# front_light.net
KiCad netlist of a schematic drawn in EAGLE
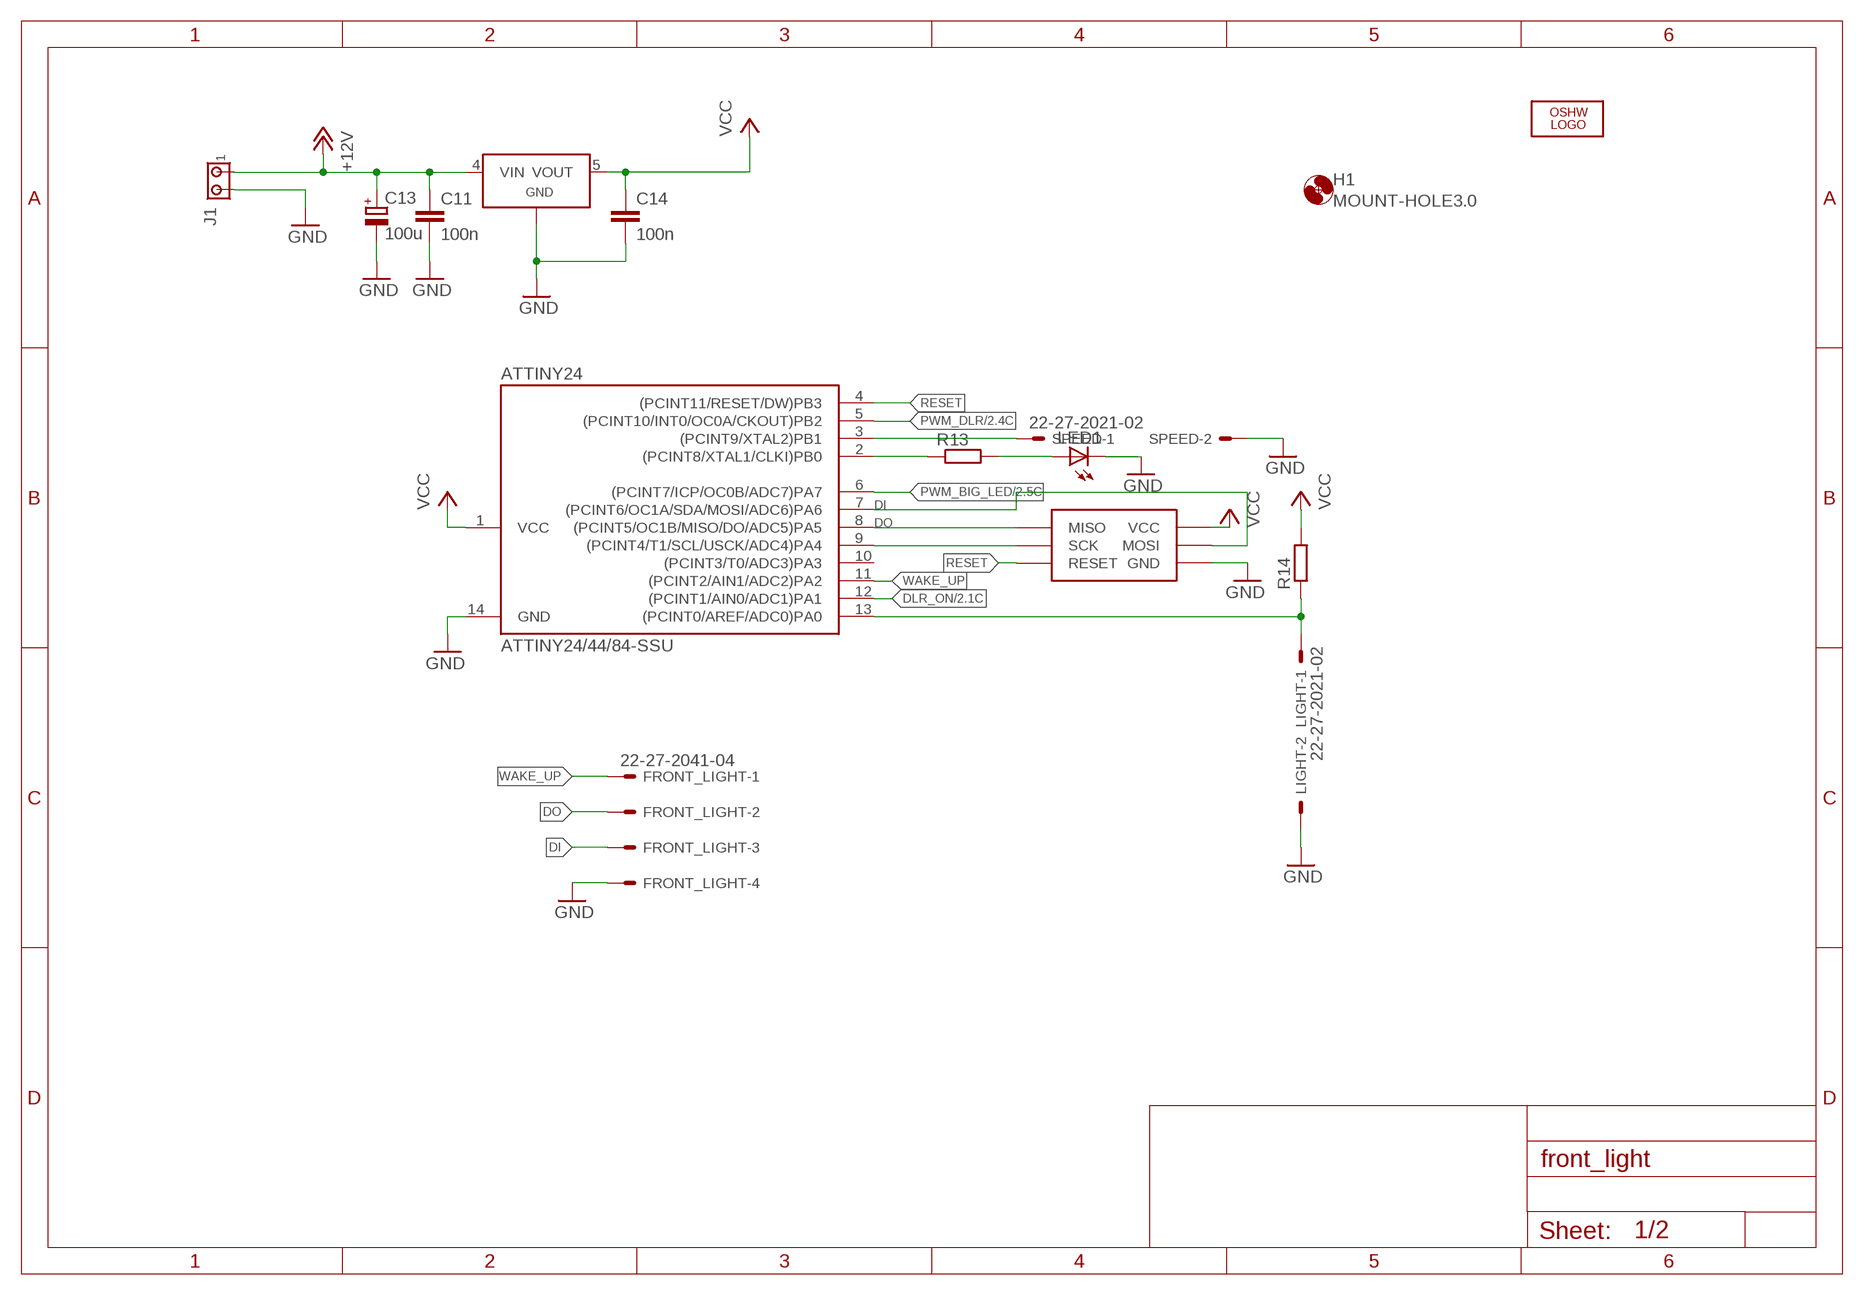
[diagram p0: schematic, sheet 1]
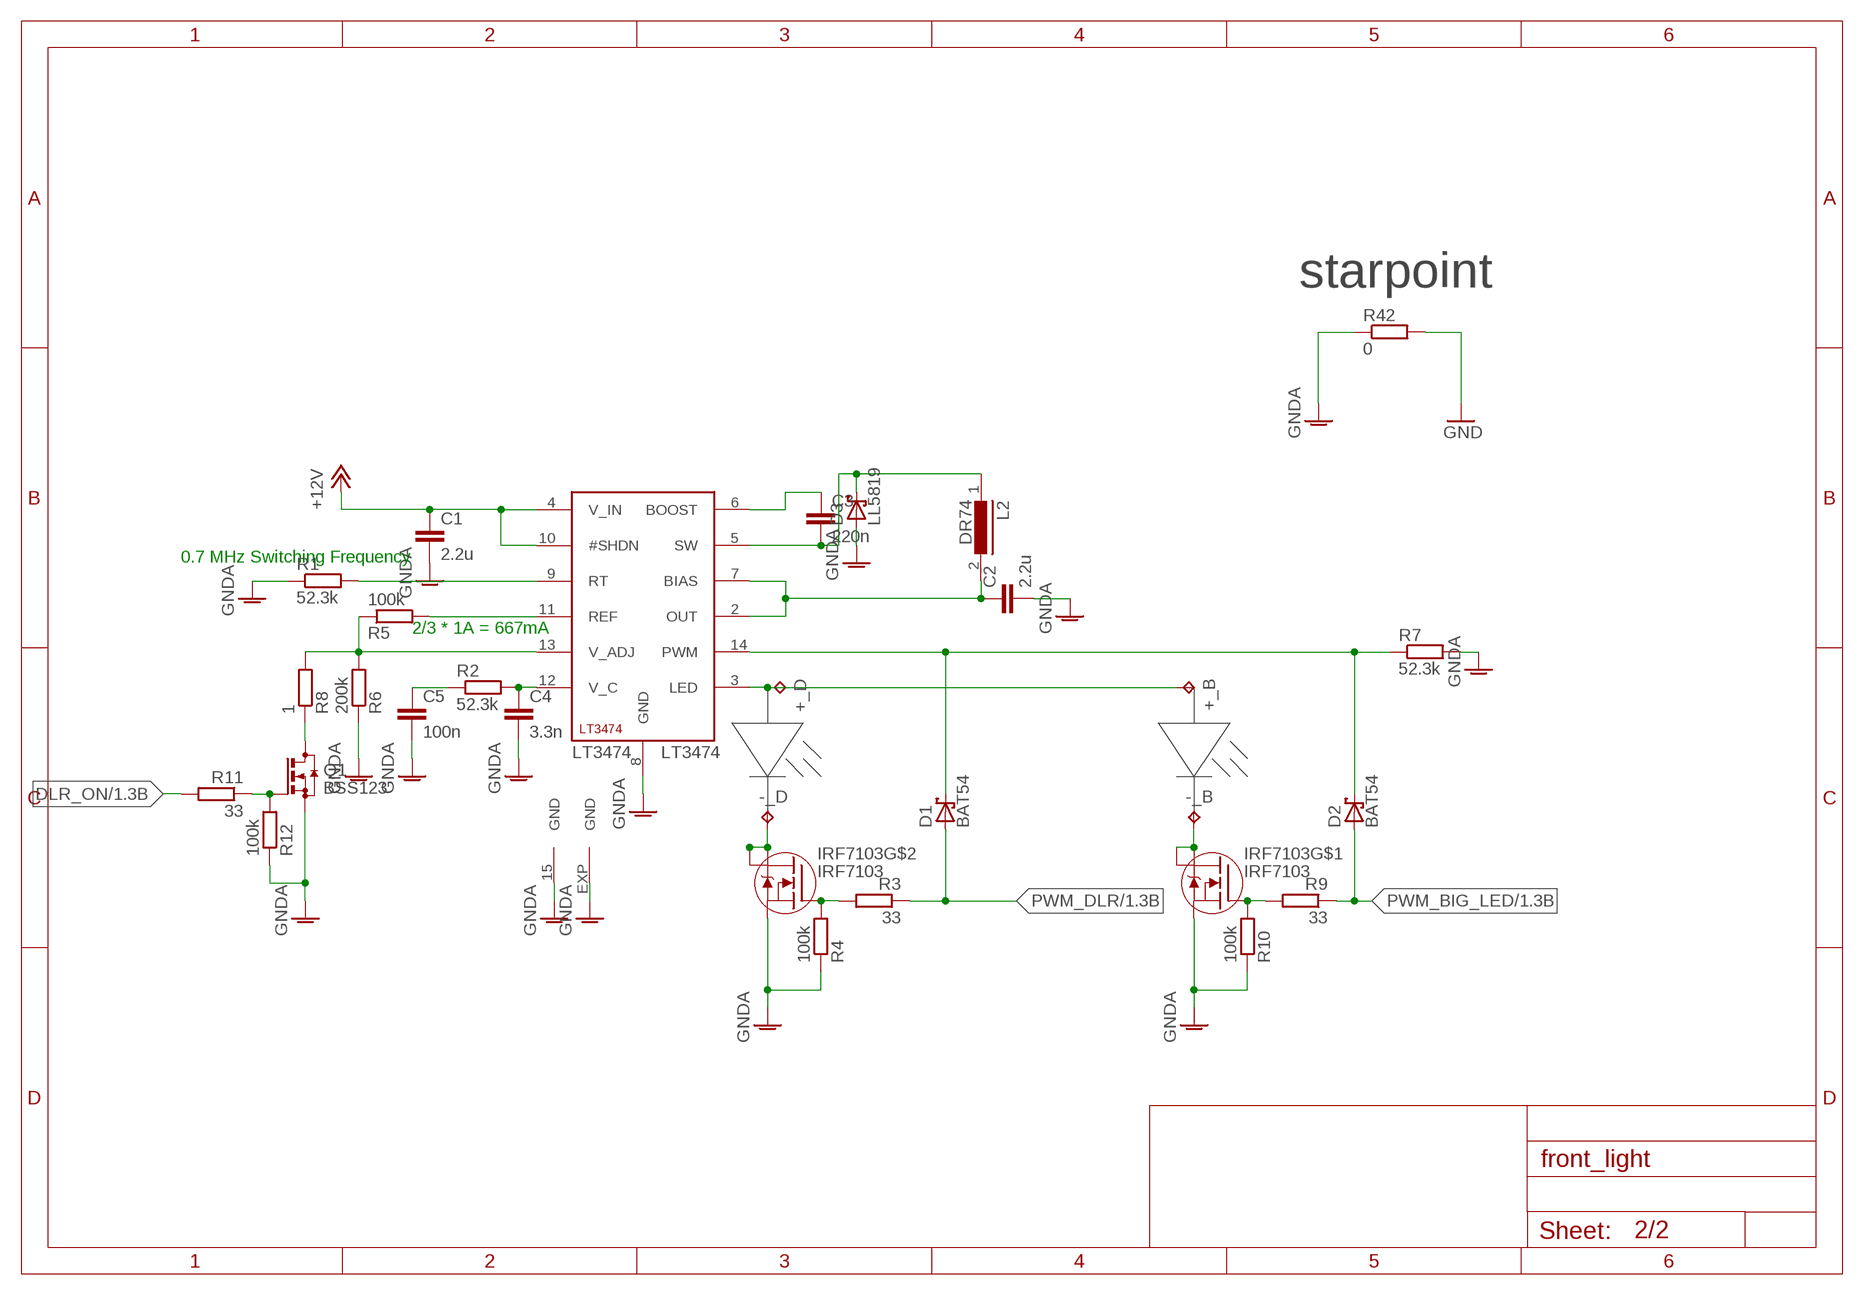
[diagram p1: schematic, sheet 2]

(export (version "E")
  (design (tool "Eeschema 10.0.6"))
  (components
    (comp (ref "+_B")
      (value "TPTP20SQ")
      (footprint "eagle-import:TP20SQ")
      (libsource (lib "eagle-import") (part "TPTP20SQ"))
    )
    (comp (ref "+_D")
      (value "TPTP20SQ")
      (footprint "eagle-import:TP20SQ")
      (libsource (lib "eagle-import") (part "TPTP20SQ"))
    )
    (comp (ref "-_B")
      (value "TPTP20SQ")
      (footprint "eagle-import:TP20SQ")
      (libsource (lib "eagle-import") (part "TPTP20SQ"))
    )
    (comp (ref "-_D")
      (value "TPTP20SQ")
      (footprint "eagle-import:TP20SQ")
      (libsource (lib "eagle-import") (part "TPTP20SQ"))
    )
    (comp (ref "C1")
      (value "2.2u")
      (footprint "eagle-import:C0805")
      (libsource (lib "eagle-import") (part "C-EUC0805"))
    )
    (comp (ref "C2")
      (value "2.2u")
      (footprint "eagle-import:C0805")
      (libsource (lib "eagle-import") (part "C-EUC0805"))
    )
    (comp (ref "C3")
      (value "220n")
      (footprint "eagle-import:C0603")
      (libsource (lib "eagle-import") (part "C-EUC0603"))
    )
    (comp (ref "C4")
      (value "3.3n")
      (footprint "eagle-import:C0603")
      (libsource (lib "eagle-import") (part "C-EUC0603"))
    )
    (comp (ref "C5")
      (value "100n")
      (footprint "eagle-import:C0603")
      (libsource (lib "eagle-import") (part "C-EUC0603"))
    )
    (comp (ref "D1")
      (value "BAT54")
      (footprint "eagle-import:SOT23")
      (libsource (lib "eagle-import") (part "BAT54"))
    )
    (comp (ref "D2")
      (value "BAT54")
      (footprint "eagle-import:SOT23")
      (libsource (lib "eagle-import") (part "BAT54"))
    )
    (comp (ref "D3")
      (value "LL5819")
      (footprint "eagle-import:MELF-MLL41")
      (libsource (lib "eagle-import") (part "DIODESCHOTTKY"))
    )
    (comp (ref "IRF7103")
      (value "IRF7103")
      (footprint "eagle-import:SO8-2")
      (libsource (lib "eagle-import") (part "IRF7103"))
    )
    (comp (ref "L2")
      (value "DR74")
      (footprint "eagle-import:DR74")
      (libsource (lib "eagle-import") (part "DR74"))
    )
    (comp (ref "LT3474")
      (value "LT3474")
      (footprint "eagle-import:TSSOP16_BA")
      (libsource (lib "eagle-import") (part "LT3474"))
    )
    (comp (ref "Q1")
      (value "BSS123")
      (footprint "eagle-import:SOT23")
      (libsource (lib "eagle-import") (part "BSS123"))
    )
    (comp (ref "R1")
      (value "52.3k")
      (footprint "eagle-import:R0603")
      (libsource (lib "eagle-import") (part "resistor_R-EU_R0603"))
    )
    (comp (ref "R2")
      (value "52.3k")
      (footprint "eagle-import:R0603")
      (libsource (lib "eagle-import") (part "resistor_R-EU_R0603"))
    )
    (comp (ref "R3")
      (value "33")
      (footprint "eagle-import:R0603")
      (libsource (lib "eagle-import") (part "resistor_R-EU_R0603"))
    )
    (comp (ref "R4")
      (value "100k")
      (footprint "eagle-import:R0603")
      (libsource (lib "eagle-import") (part "resistor_R-EU_R0603"))
    )
    (comp (ref "R5")
      (value "100k")
      (footprint "eagle-import:R0603")
      (libsource (lib "eagle-import") (part "resistor_R-EU_R0603"))
    )
    (comp (ref "R6")
      (value "200k")
      (footprint "eagle-import:R0603")
      (libsource (lib "eagle-import") (part "resistor_R-EU_R0603"))
    )
    (comp (ref "R7")
      (value "52.3k")
      (footprint "eagle-import:R0603")
      (libsource (lib "eagle-import") (part "resistor_R-EU_R0603"))
    )
    (comp (ref "R8")
      (value "1")
      (footprint "eagle-import:R0603")
      (libsource (lib "eagle-import") (part "resistor_R-EU_R0603"))
    )
    (comp (ref "R9")
      (value "33")
      (footprint "eagle-import:R0603")
      (libsource (lib "eagle-import") (part "resistor_R-EU_R0603"))
    )
    (comp (ref "R10")
      (value "100k")
      (footprint "eagle-import:R0603")
      (libsource (lib "eagle-import") (part "resistor_R-EU_R0603"))
    )
    (comp (ref "R11")
      (value "33")
      (footprint "eagle-import:R0603")
      (libsource (lib "eagle-import") (part "resistor_R-EU_R0603"))
    )
    (comp (ref "R12")
      (value "100k")
      (footprint "eagle-import:R0603")
      (libsource (lib "eagle-import") (part "resistor_R-EU_R0603"))
    )
    (comp (ref "R42")
      (value "0")
      (footprint "eagle-import:R0603")
      (libsource (lib "eagle-import") (part "R-EU_R0603"))
    )
    (comp (ref "ATTINY24")
      (value "ATTINY24/44/84-SSU")
      (footprint "eagle-import:SOIC14")
      (libsource (lib "eagle-import") (part "ATTINY24/44/84-SSU"))
    )
    (comp (ref "C11")
      (value "100n")
      (footprint "eagle-import:C0603")
      (libsource (lib "eagle-import") (part "C-EUC0603"))
    )
    (comp (ref "C13")
      (value "100u")
      (footprint "eagle-import:PANASONIC_E")
      (libsource (lib "eagle-import") (part "CPOL-EUE"))
    )
    (comp (ref "C14")
      (value "100n")
      (footprint "eagle-import:C0603")
      (libsource (lib "eagle-import") (part "C-EUC0603"))
    )
    (comp (ref "FRONT_LIGHT")
      (value "22-27-2041-04")
      (footprint "eagle-import:6410-04")
      (libsource (lib "eagle-import") (part "22-?-0427-2041"))
    )
    (comp (ref "H1")
      (value "MOUNT-HOLE3.0")
      (footprint "eagle-import:3,0")
      (libsource (lib "eagle-import") (part "MOUNT-HOLE3.0"))
    )
    (comp (ref "J1")
      (value "MTA02-156")
      (footprint "eagle-import:1X2MTA")
      (libsource (lib "eagle-import") (part "MTA02-156"))
    )
    (comp (ref "LED1")
      (value "LEDCHIPLED_0603")
      (footprint "eagle-import:CHIPLED_0603")
      (libsource (lib "eagle-import") (part "LEDCHIPLED_0603"))
    )
    (comp (ref "LIGHT")
      (value "22-27-2021-02")
      (footprint "eagle-import:6410-02")
      (libsource (lib "eagle-import") (part "22-?-0227-2021"))
    )
    (comp (ref "LOGO2")
      (value "OSHW_LOGO_6MILX0150-NT")
      (footprint "eagle-import:OSHW_6X150_NOTEXT")
      (libsource (lib "eagle-import") (part "OSHW_LOGO_6MILX0150-NT"))
    )
    (comp (ref "R13")
      (value "R-EU_R0603")
      (footprint "eagle-import:R0603")
      (libsource (lib "eagle-import") (part "resistor_R-EU_R0603"))
    )
    (comp (ref "R14")
      (value "R-EU_R0603")
      (footprint "eagle-import:R0603")
      (libsource (lib "eagle-import") (part "resistor_R-EU_R0603"))
    )
    (comp (ref "SPEED")
      (value "22-27-2021-02")
      (footprint "eagle-import:6410-02")
      (libsource (lib "eagle-import") (part "22-?-0227-2021"))
    )
    (comp (ref "U$1")
      (value "TPS71530")
      (footprint "eagle-import:SOT23-DBV")
      (libsource (lib "eagle-import") (part "TPS71530"))
    )
    (comp (ref "U$2")
      (value "ISP_SPECIALS")
      (footprint "eagle-import:ISP_RM2_00_STRAIGHT")
      (libsource (lib "eagle-import") (part "ISP_SPECIALS"))
    )
  )
  (nets
    (net (code "1") (name "+12V") (class "Default")
      (node (ref "C1") (pin "1") (pinfunction "1_1") (pintype "passive"))
      (node (ref "C11") (pin "1") (pinfunction "1_1") (pintype "passive"))
      (node (ref "C13") (pin "+") (pinfunction "+_+") (pintype "passive"))
      (node (ref "J1") (pin "1") (pinfunction "1_1") (pintype "passive"))
      (node (ref "LT3474") (pin "10") (pinfunction "#SHDN_10") (pintype "passive"))
      (node (ref "LT3474") (pin "4") (pinfunction "V_IN_4") (pintype "passive"))
      (node (ref "U$1") (pin "4") (pinfunction "VIN_4") (pintype "power_in"))
    )
    (net (code "2") (name "DI") (class "Default")
      (node (ref "ATTINY24") (pin "7") (pinfunction "(PCINT6/OC1A/SDA/MOSI/ADC6)PA6_7") (pintype "bidirectional"))
      (node (ref "FRONT_LIGHT") (pin "3") (pinfunction "S_3") (pintype "passive"))
      (node (ref "U$2") (pin "MOSI") (pinfunction "MOSI_MOSI") (pintype "bidirectional"))
    )
    (net (code "3") (name "DLR_ON") (class "Default")
      (node (ref "ATTINY24") (pin "12") (pinfunction "(PCINT1/AIN0/ADC1)PA1_12") (pintype "bidirectional"))
      (node (ref "R11") (pin "2") (pinfunction "2_2") (pintype "passive"))
    )
    (net (code "4") (name "DO") (class "Default")
      (node (ref "ATTINY24") (pin "8") (pinfunction "(PCINT5/OC1B/MISO/DO/ADC5)PA5_8") (pintype "bidirectional"))
      (node (ref "FRONT_LIGHT") (pin "2") (pinfunction "S_2") (pintype "passive"))
      (node (ref "U$2") (pin "RESET") (pinfunction "MISO_RESET") (pintype "bidirectional"))
    )
    (net (code "5") (name "GND") (class "Default")
      (node (ref "ATTINY24") (pin "14") (pinfunction "GND_14") (pintype "power_in"))
      (node (ref "C11") (pin "2") (pinfunction "2_2") (pintype "passive"))
      (node (ref "C13") (pin "-") (pinfunction "-_-") (pintype "passive"))
      (node (ref "C14") (pin "2") (pinfunction "2_2") (pintype "passive"))
      (node (ref "FRONT_LIGHT") (pin "4") (pinfunction "S_4") (pintype "passive"))
      (node (ref "J1") (pin "2") (pinfunction "2_2") (pintype "passive"))
      (node (ref "LED1") (pin "C") (pinfunction "C_C") (pintype "passive"))
      (node (ref "LIGHT") (pin "2") (pinfunction "S_2") (pintype "passive"))
      (node (ref "R42") (pin "2") (pinfunction "2_2") (pintype "passive"))
      (node (ref "SPEED") (pin "2") (pinfunction "S_2") (pintype "passive"))
      (node (ref "U$1") (pin "2") (pinfunction "GND_2") (pintype "power_in"))
      (node (ref "U$2") (pin "VCC") (pinfunction "GND_VCC") (pintype "bidirectional"))
    )
    (net (code "6") (name "GNDA") (class "Default")
      (node (ref "C1") (pin "2") (pinfunction "2_2") (pintype "passive"))
      (node (ref "C2") (pin "2") (pinfunction "2_2") (pintype "passive"))
      (node (ref "C4") (pin "2") (pinfunction "2_2") (pintype "passive"))
      (node (ref "C5") (pin "2") (pinfunction "2_2") (pintype "passive"))
      (node (ref "D3") (pin "A") (pinfunction "A_A") (pintype "passive"))
      (node (ref "IRF7103") (pin "1") (pinfunction "S_1") (pintype "bidirectional"))
      (node (ref "IRF7103") (pin "3") (pinfunction "S_3") (pintype "bidirectional"))
      (node (ref "LT3474") (pin "15") (pinfunction "GND_15") (pintype "power_in"))
      (node (ref "LT3474") (pin "8") (pinfunction "GND_8") (pintype "power_in"))
      (node (ref "LT3474") (pin "EXP") (pinfunction "GND_EXP") (pintype "power_in"))
      (node (ref "Q1") (pin "2") (pinfunction "S_2") (pintype "passive"))
      (node (ref "R1") (pin "1") (pinfunction "1_1") (pintype "passive"))
      (node (ref "R10") (pin "1") (pinfunction "1_1") (pintype "passive"))
      (node (ref "R12") (pin "1") (pinfunction "1_1") (pintype "passive"))
      (node (ref "R4") (pin "1") (pinfunction "1_1") (pintype "passive"))
      (node (ref "R42") (pin "1") (pinfunction "1_1") (pintype "passive"))
      (node (ref "R6") (pin "1") (pinfunction "1_1") (pintype "passive"))
      (node (ref "R7") (pin "2") (pinfunction "2_2") (pintype "passive"))
    )
    (net (code "7") (name "Net-(-_B-PadTP)") (class "Default")
      (node (ref "-_B") (pin "TP") (pinfunction "TP_TP") (pintype "input"))
      (node (ref "IRF7103") (pin "7") (pinfunction "D_7") (pintype "bidirectional"))
      (node (ref "IRF7103") (pin "8") (pinfunction "D_8") (pintype "bidirectional"))
    )
    (net (code "8") (name "Net-(-_D-PadTP)") (class "Default")
      (node (ref "-_D") (pin "TP") (pinfunction "TP_TP") (pintype "input"))
      (node (ref "IRF7103") (pin "5") (pinfunction "D_5") (pintype "bidirectional"))
      (node (ref "IRF7103") (pin "6") (pinfunction "D_6") (pintype "bidirectional"))
    )
    (net (code "9") (name "Net-(ATTINY24-(PCINT0{slash}AREF{slash}ADC0)PA0)") (class "Default")
      (node (ref "ATTINY24") (pin "13") (pinfunction "(PCINT0/AREF/ADC0)PA0_13") (pintype "bidirectional"))
      (node (ref "LIGHT") (pin "1") (pinfunction "S_1") (pintype "passive"))
      (node (ref "R14") (pin "1") (pinfunction "1_1") (pintype "passive"))
    )
    (net (code "10") (name "Net-(ATTINY24-(PCINT4{slash}T1{slash}SCL{slash}USCK{slash}ADC4)PA4)") (class "Default")
      (node (ref "ATTINY24") (pin "9") (pinfunction "(PCINT4/T1/SCL/USCK/ADC4)PA4_9") (pintype "bidirectional"))
      (node (ref "U$2") (pin "SCK") (pinfunction "SCK_SCK") (pintype "bidirectional"))
    )
    (net (code "11") (name "Net-(ATTINY24-(PCINT8{slash}XTAL1{slash}CLKI)PB0)") (class "Default")
      (node (ref "ATTINY24") (pin "2") (pinfunction "(PCINT8/XTAL1/CLKI)PB0_2") (pintype "bidirectional"))
      (node (ref "R13") (pin "1") (pinfunction "1_1") (pintype "passive"))
    )
    (net (code "12") (name "Net-(ATTINY24-(PCINT9{slash}XTAL2)PB1)") (class "Default")
      (node (ref "ATTINY24") (pin "3") (pinfunction "(PCINT9/XTAL2)PB1_3") (pintype "bidirectional"))
      (node (ref "SPEED") (pin "1") (pinfunction "S_1") (pintype "passive"))
    )
    (net (code "13") (name "Net-(C5-Pad1)") (class "Default")
      (node (ref "C5") (pin "1") (pinfunction "1_1") (pintype "passive"))
      (node (ref "R2") (pin "1") (pinfunction "1_1") (pintype "passive"))
    )
    (net (code "14") (name "Net-(D1-C)") (class "Default")
      (node (ref "D1") (pin "3") (pinfunction "C_3") (pintype "passive"))
      (node (ref "D2") (pin "3") (pinfunction "C_3") (pintype "passive"))
      (node (ref "LT3474") (pin "14") (pinfunction "PWM_14") (pintype "passive"))
      (node (ref "R7") (pin "1") (pinfunction "1_1") (pintype "passive"))
    )
    (net (code "15") (name "Net-(IRF7103A-G)") (class "Default")
      (node (ref "IRF7103") (pin "2") (pinfunction "G_2") (pintype "bidirectional"))
      (node (ref "R10") (pin "2") (pinfunction "2_2") (pintype "passive"))
      (node (ref "R9") (pin "2") (pinfunction "2_2") (pintype "passive"))
    )
    (net (code "16") (name "Net-(IRF7103B-G)") (class "Default")
      (node (ref "IRF7103") (pin "4") (pinfunction "G_4") (pintype "bidirectional"))
      (node (ref "R3") (pin "2") (pinfunction "2_2") (pintype "passive"))
      (node (ref "R4") (pin "2") (pinfunction "2_2") (pintype "passive"))
    )
    (net (code "17") (name "Net-(LED1-PadA)") (class "Default")
      (node (ref "LED1") (pin "A") (pinfunction "A_A") (pintype "passive"))
      (node (ref "R13") (pin "2") (pinfunction "2_2") (pintype "passive"))
    )
    (net (code "18") (name "Net-(LT3474A-BIAS)") (class "Default")
      (node (ref "C2") (pin "1") (pinfunction "1_1") (pintype "passive"))
      (node (ref "L2") (pin "2") (pinfunction "2_2") (pintype "passive"))
      (node (ref "LT3474") (pin "2") (pinfunction "OUT_2") (pintype "passive"))
      (node (ref "LT3474") (pin "7") (pinfunction "BIAS_7") (pintype "passive"))
    )
    (net (code "19") (name "Net-(LT3474A-BOOST)") (class "Default")
      (node (ref "C3") (pin "1") (pinfunction "1_1") (pintype "passive"))
      (node (ref "LT3474") (pin "6") (pinfunction "BOOST_6") (pintype "passive"))
    )
    (net (code "20") (name "Net-(LT3474A-LED)") (class "Default")
      (node (ref "+_B") (pin "TP") (pinfunction "TP_TP") (pintype "input"))
      (node (ref "+_D") (pin "TP") (pinfunction "TP_TP") (pintype "input"))
      (node (ref "LT3474") (pin "3") (pinfunction "LED_3") (pintype "passive"))
    )
    (net (code "21") (name "Net-(LT3474A-REF)") (class "Default")
      (node (ref "LT3474") (pin "11") (pinfunction "REF_11") (pintype "passive"))
      (node (ref "R5") (pin "2") (pinfunction "2_2") (pintype "passive"))
    )
    (net (code "22") (name "Net-(LT3474A-RT)") (class "Default")
      (node (ref "LT3474") (pin "9") (pinfunction "RT_9") (pintype "passive"))
      (node (ref "R1") (pin "2") (pinfunction "2_2") (pintype "passive"))
    )
    (net (code "23") (name "Net-(LT3474A-SW)") (class "Default")
      (node (ref "C3") (pin "2") (pinfunction "2_2") (pintype "passive"))
      (node (ref "D3") (pin "C") (pinfunction "C_C") (pintype "passive"))
      (node (ref "L2") (pin "1") (pinfunction "1_1") (pintype "passive"))
      (node (ref "LT3474") (pin "5") (pinfunction "SW_5") (pintype "passive"))
    )
    (net (code "24") (name "Net-(LT3474A-V_ADJ)") (class "Default")
      (node (ref "LT3474") (pin "13") (pinfunction "V_ADJ_13") (pintype "passive"))
      (node (ref "R5") (pin "1") (pinfunction "1_1") (pintype "passive"))
      (node (ref "R6") (pin "2") (pinfunction "2_2") (pintype "passive"))
      (node (ref "R8") (pin "2") (pinfunction "2_2") (pintype "passive"))
    )
    (net (code "25") (name "Net-(LT3474A-V_C)") (class "Default")
      (node (ref "C4") (pin "1") (pinfunction "1_1") (pintype "passive"))
      (node (ref "LT3474") (pin "12") (pinfunction "V_C_12") (pintype "passive"))
      (node (ref "R2") (pin "2") (pinfunction "2_2") (pintype "passive"))
    )
    (net (code "26") (name "Net-(Q1-D)") (class "Default")
      (node (ref "Q1") (pin "3") (pinfunction "D_3") (pintype "passive"))
      (node (ref "R8") (pin "1") (pinfunction "1_1") (pintype "passive"))
    )
    (net (code "27") (name "Net-(Q1-G)") (class "Default")
      (node (ref "Q1") (pin "1") (pinfunction "G_1") (pintype "passive"))
      (node (ref "R11") (pin "1") (pinfunction "1_1") (pintype "passive"))
      (node (ref "R12") (pin "2") (pinfunction "2_2") (pintype "passive"))
    )
    (net (code "28") (name "PWM_BIG_LED") (class "Default")
      (node (ref "ATTINY24") (pin "6") (pinfunction "(PCINT7/ICP/OC0B/ADC7)PA7_6") (pintype "bidirectional"))
      (node (ref "D2") (pin "1") (pinfunction "A_1") (pintype "passive"))
      (node (ref "R9") (pin "1") (pinfunction "1_1") (pintype "passive"))
    )
    (net (code "29") (name "PWM_DLR") (class "Default")
      (node (ref "ATTINY24") (pin "5") (pinfunction "(PCINT10/INT0/OC0A/CKOUT)PB2_5") (pintype "bidirectional"))
      (node (ref "D1") (pin "1") (pinfunction "A_1") (pintype "passive"))
      (node (ref "R3") (pin "1") (pinfunction "1_1") (pintype "passive"))
    )
    (net (code "30") (name "RESET") (class "Default")
      (node (ref "ATTINY24") (pin "4") (pinfunction "(PCINT11/RESET/DW)PB3_4") (pintype "bidirectional"))
      (node (ref "U$2") (pin "MISO") (pinfunction "RESET_MISO") (pintype "bidirectional"))
    )
    (net (code "31") (name "VCC") (class "Default")
      (node (ref "ATTINY24") (pin "1") (pinfunction "VCC_1") (pintype "power_in"))
      (node (ref "C14") (pin "1") (pinfunction "1_1") (pintype "passive"))
      (node (ref "R14") (pin "2") (pinfunction "2_2") (pintype "passive"))
      (node (ref "U$1") (pin "5") (pinfunction "VOUT_5") (pintype "power_in"))
      (node (ref "U$2") (pin "GND") (pinfunction "VCC_GND") (pintype "bidirectional"))
    )
    (net (code "32") (name "WAKE_UP") (class "Default")
      (node (ref "ATTINY24") (pin "11") (pinfunction "(PCINT2/AIN1/ADC2)PA2_11") (pintype "bidirectional"))
      (node (ref "FRONT_LIGHT") (pin "1") (pinfunction "S_1") (pintype "passive"))
    )
    (net (code "33") (name "unconnected-(ATTINY24-(PCINT3{slash}T0{slash}ADC3)PA3-Pad10)") (class "Default")
      (node (ref "ATTINY24") (pin "10") (pinfunction "(PCINT3/T0/ADC3)PA3_10") (pintype "bidirectional"))
    )
  )
)
